# 1010829PA_HVFlyback_GD_Testboard_Overvie.net
KiCad netlist of a schematic drawn in Altium Designer
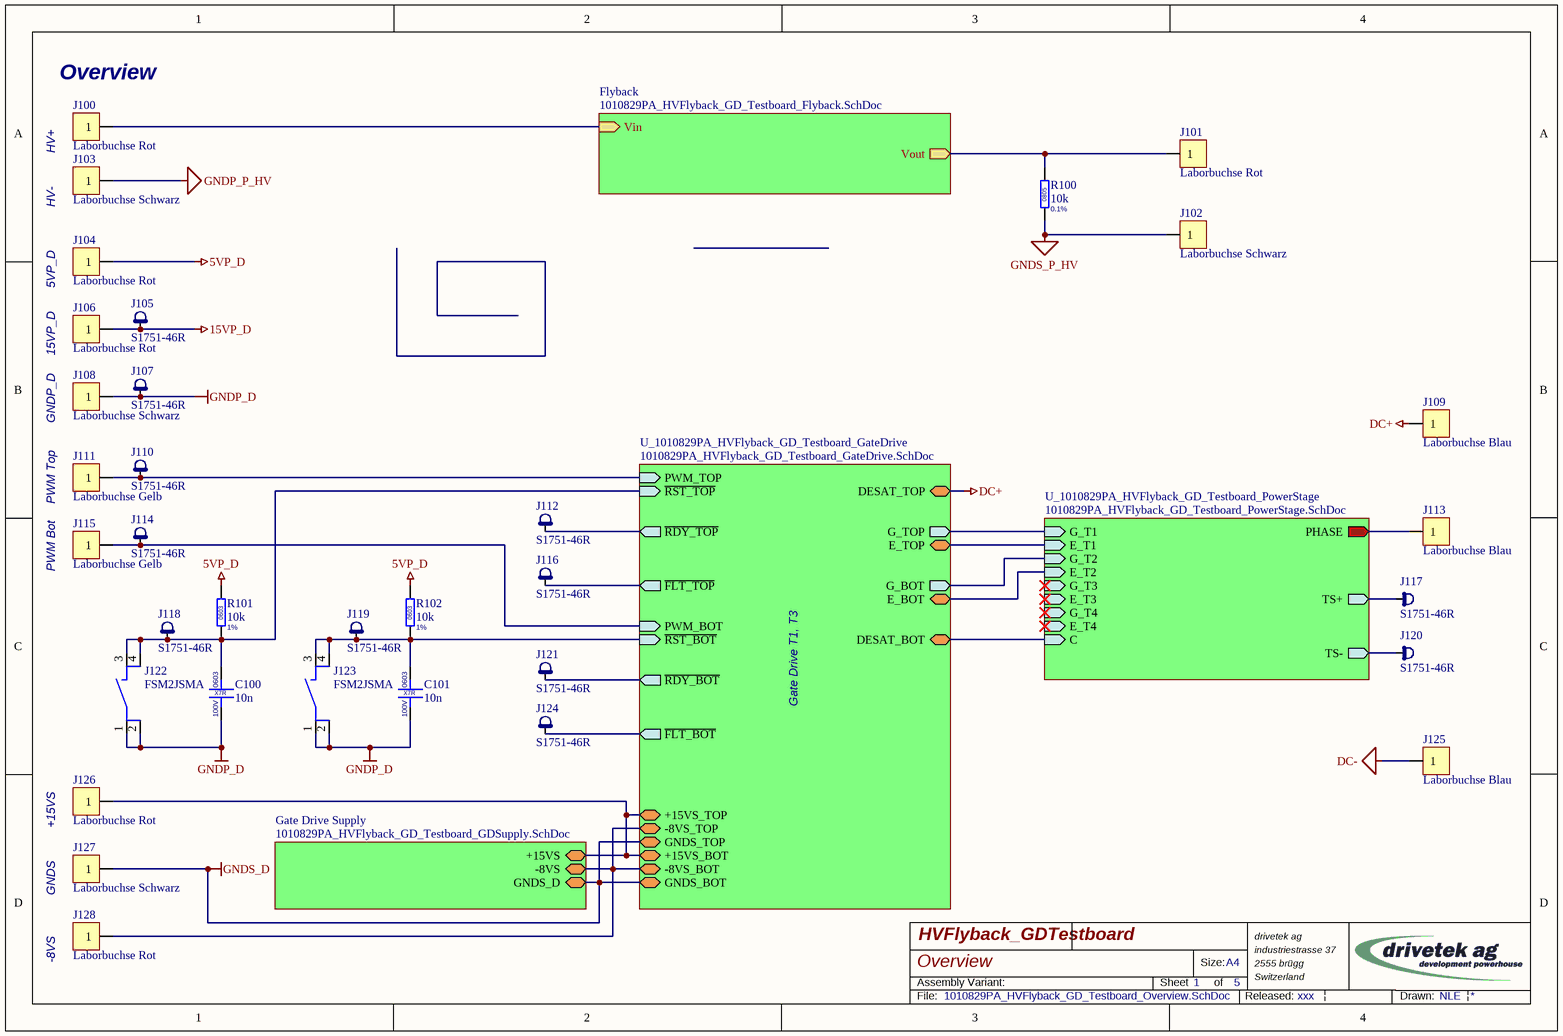
[diagram p0: 1010829PA_HVFlyback_GD_Testboard_Overview.SchDoc]

(export (version "E")
  (design (tool "Eeschema 10.0.6"))
  (components
    (comp (ref "C100")
      (value "10n")
      (footprint "02_0603_DRK_1-7x1-0x0-9")
      (fields
        (field (name "CASENAME") "0603")
        (field (name "TYPE3") "X7R")
        (field (name "VOLTAGE") "100V")
        (field (name "PART NUMBER") "02-0313")
        (field (name "TOLERANCE") "10")
        (field (name "AUTHOR") "RLE")
      )
      (libsource (lib "drivetek") (part "02_CAP"))
    )
    (comp (ref "C101")
      (value "10n")
      (footprint "02_0603_DRK_1-7x1-0x0-9")
      (fields
        (field (name "CASENAME") "0603")
        (field (name "TYPE3") "X7R")
        (field (name "VOLTAGE") "100V")
        (field (name "PART NUMBER") "02-0313")
        (field (name "TOLERANCE") "10")
        (field (name "AUTHOR") "RLE")
      )
      (libsource (lib "drivetek") (part "02_CAP"))
    )
    (comp (ref "J100")
      (value "Laborbuchse Rot")
      (footprint "13_CON_DRK_DELTRON-571-0100-4mm-Buchse")
      (fields
        (field (name "PART NUMBER") "13-0252")
        (field (name "VOLTAGE") "250V")
        (field (name "AUTHOR") "MFR")
      )
      (libsource (lib "drivetek") (part "13_CON_1"))
    )
    (comp (ref "J101")
      (value "Laborbuchse Rot")
      (footprint "13_CON_DRK_DELTRON-571-0100-4mm-Buchse")
      (fields
        (field (name "PART NUMBER") "13-0252")
        (field (name "VOLTAGE") "250V")
        (field (name "AUTHOR") "MFR")
      )
      (libsource (lib "") (part "13_CON_1_1"))
    )
    (comp (ref "J102")
      (value "Laborbuchse Schwarz")
      (footprint "13_CON_DRK_DELTRON-571-0100-4mm-Buchse")
      (fields
        (field (name "PART NUMBER") "13-0253")
        (field (name "VOLTAGE") "250V")
        (field (name "AUTHOR") "MFR")
      )
      (libsource (lib "") (part "13_CON_1_1"))
    )
    (comp (ref "J103")
      (value "Laborbuchse Schwarz")
      (footprint "13_CON_DRK_DELTRON-571-0100-4mm-Buchse")
      (fields
        (field (name "PART NUMBER") "13-0253")
        (field (name "VOLTAGE") "250V")
        (field (name "AUTHOR") "MFR")
      )
      (libsource (lib "drivetek") (part "13_CON_1"))
    )
    (comp (ref "J104")
      (value "Laborbuchse Rot")
      (footprint "13_CON_DRK_DELTRON-571-0100-4mm-Buchse")
      (fields
        (field (name "PART NUMBER") "13-0252")
        (field (name "VOLTAGE") "250V")
        (field (name "AUTHOR") "MFR")
      )
      (libsource (lib "drivetek") (part "13_CON_1"))
    )
    (comp (ref "J105")
      (value "S1751-46R")
      (footprint "13_PAD_DRK_HARWIN_S1751-46")
      (description "Probe Hook")
      (fields (field (name "PART NUMBER") "13-0487") (field (name "AUTHOR") "CSI"))
      (libsource (lib "drivetek") (part "13_ProbeHook"))
    )
    (comp (ref "J106")
      (value "Laborbuchse Rot")
      (footprint "13_CON_DRK_DELTRON-571-0100-4mm-Buchse")
      (fields
        (field (name "PART NUMBER") "13-0252")
        (field (name "VOLTAGE") "250V")
        (field (name "AUTHOR") "MFR")
      )
      (libsource (lib "drivetek") (part "13_CON_1"))
    )
    (comp (ref "J107")
      (value "S1751-46R")
      (footprint "13_PAD_DRK_HARWIN_S1751-46")
      (description "Probe Hook")
      (fields (field (name "PART NUMBER") "13-0487") (field (name "AUTHOR") "CSI"))
      (libsource (lib "drivetek") (part "13_ProbeHook"))
    )
    (comp (ref "J108")
      (value "Laborbuchse Schwarz")
      (footprint "13_CON_DRK_DELTRON-571-0100-4mm-Buchse")
      (fields
        (field (name "PART NUMBER") "13-0253")
        (field (name "VOLTAGE") "250V")
        (field (name "AUTHOR") "MFR")
      )
      (libsource (lib "drivetek") (part "13_CON_1"))
    )
    (comp (ref "J109")
      (value "Laborbuchse Blau")
      (footprint "13_CON_DRK_DELTRON-571-0100-4mm-Buchse")
      (fields
        (field (name "PART NUMBER") "13-0507")
        (field (name "VOLTAGE") "250V")
        (field (name "AUTHOR") "RLE")
      )
      (libsource (lib "") (part "13_CON_1_1"))
    )
    (comp (ref "J110")
      (value "S1751-46R")
      (footprint "13_PAD_DRK_HARWIN_S1751-46")
      (description "Probe Hook")
      (fields (field (name "PART NUMBER") "13-0487") (field (name "AUTHOR") "CSI"))
      (libsource (lib "drivetek") (part "13_ProbeHook"))
    )
    (comp (ref "J111")
      (value "Laborbuchse Gelb")
      (footprint "13_CON_DRK_DELTRON-571-0100-4mm-Buchse")
      (fields
        (field (name "PART NUMBER") "13-0506")
        (field (name "VOLTAGE") "250V")
        (field (name "AUTHOR") "RLE")
      )
      (libsource (lib "drivetek") (part "13_CON_1"))
    )
    (comp (ref "J112")
      (value "S1751-46R")
      (footprint "13_PAD_DRK_HARWIN_S1751-46")
      (description "Probe Hook")
      (fields (field (name "PART NUMBER") "13-0487") (field (name "AUTHOR") "CSI"))
      (libsource (lib "drivetek") (part "13_ProbeHook"))
    )
    (comp (ref "J113")
      (value "Laborbuchse Blau")
      (footprint "13_CON_DRK_DELTRON-571-0100-4mm-Buchse")
      (fields
        (field (name "PART NUMBER") "13-0507")
        (field (name "VOLTAGE") "250V")
        (field (name "AUTHOR") "RLE")
      )
      (libsource (lib "") (part "13_CON_1_1"))
    )
    (comp (ref "J114")
      (value "S1751-46R")
      (footprint "13_PAD_DRK_HARWIN_S1751-46")
      (description "Probe Hook")
      (fields (field (name "PART NUMBER") "13-0487") (field (name "AUTHOR") "CSI"))
      (libsource (lib "drivetek") (part "13_ProbeHook"))
    )
    (comp (ref "J115")
      (value "Laborbuchse Gelb")
      (footprint "13_CON_DRK_DELTRON-571-0100-4mm-Buchse")
      (fields
        (field (name "PART NUMBER") "13-0506")
        (field (name "VOLTAGE") "250V")
        (field (name "AUTHOR") "RLE")
      )
      (libsource (lib "drivetek") (part "13_CON_1"))
    )
    (comp (ref "J116")
      (value "S1751-46R")
      (footprint "13_PAD_DRK_HARWIN_S1751-46")
      (description "Probe Hook")
      (fields (field (name "PART NUMBER") "13-0487") (field (name "AUTHOR") "CSI"))
      (libsource (lib "drivetek") (part "13_ProbeHook"))
    )
    (comp (ref "J117")
      (value "S1751-46R")
      (footprint "13_PAD_DRK_HARWIN_S1751-46")
      (description "Probe Hook")
      (fields (field (name "PART NUMBER") "13-0487") (field (name "AUTHOR") "CSI"))
      (libsource (lib "drivetek") (part "13_ProbeHook"))
    )
    (comp (ref "J118")
      (value "S1751-46R")
      (footprint "13_PAD_DRK_HARWIN_S1751-46")
      (description "Probe Hook")
      (fields (field (name "PART NUMBER") "13-0487") (field (name "AUTHOR") "CSI"))
      (libsource (lib "drivetek") (part "13_ProbeHook"))
    )
    (comp (ref "J119")
      (value "S1751-46R")
      (footprint "13_PAD_DRK_HARWIN_S1751-46")
      (description "Probe Hook")
      (fields (field (name "PART NUMBER") "13-0487") (field (name "AUTHOR") "CSI"))
      (libsource (lib "drivetek") (part "13_ProbeHook"))
    )
    (comp (ref "J120")
      (value "S1751-46R")
      (footprint "13_PAD_DRK_HARWIN_S1751-46")
      (description "Probe Hook")
      (fields (field (name "PART NUMBER") "13-0487") (field (name "AUTHOR") "CSI"))
      (libsource (lib "drivetek") (part "13_ProbeHook"))
    )
    (comp (ref "J121")
      (value "S1751-46R")
      (footprint "13_PAD_DRK_HARWIN_S1751-46")
      (description "Probe Hook")
      (fields (field (name "PART NUMBER") "13-0487") (field (name "AUTHOR") "CSI"))
      (libsource (lib "drivetek") (part "13_ProbeHook"))
    )
    (comp (ref "J122")
      (value "FSM2JSMA")
      (footprint "10_SW_DRK_TYCO-FSM2JSMA")
      (fields
        (field (name "PART NUMBER") "10-0001")
        (field (name "VOLTAGE") "24V")
        (field (name "AUTHOR") "CBA")
      )
      (libsource (lib "drivetek") (part "10_SPNO_A12-B34"))
    )
    (comp (ref "J123")
      (value "FSM2JSMA")
      (footprint "10_SW_DRK_TYCO-FSM2JSMA")
      (fields
        (field (name "PART NUMBER") "10-0001")
        (field (name "VOLTAGE") "24V")
        (field (name "AUTHOR") "CBA")
      )
      (libsource (lib "drivetek") (part "10_SPNO_A12-B34"))
    )
    (comp (ref "J124")
      (value "S1751-46R")
      (footprint "13_PAD_DRK_HARWIN_S1751-46")
      (description "Probe Hook")
      (fields (field (name "PART NUMBER") "13-0487") (field (name "AUTHOR") "CSI"))
      (libsource (lib "drivetek") (part "13_ProbeHook"))
    )
    (comp (ref "J125")
      (value "Laborbuchse Blau")
      (footprint "13_CON_DRK_DELTRON-571-0100-4mm-Buchse")
      (fields
        (field (name "PART NUMBER") "13-0507")
        (field (name "VOLTAGE") "250V")
        (field (name "AUTHOR") "RLE")
      )
      (libsource (lib "") (part "13_CON_1_1"))
    )
    (comp (ref "J126")
      (value "Laborbuchse Rot")
      (footprint "13_CON_DRK_DELTRON-571-0100-4mm-Buchse")
      (fields
        (field (name "PART NUMBER") "13-0252")
        (field (name "VOLTAGE") "250V")
        (field (name "AUTHOR") "MFR")
      )
      (libsource (lib "drivetek") (part "13_CON_1"))
    )
    (comp (ref "J127")
      (value "Laborbuchse Schwarz")
      (footprint "13_CON_DRK_DELTRON-571-0100-4mm-Buchse")
      (fields
        (field (name "PART NUMBER") "13-0253")
        (field (name "VOLTAGE") "250V")
        (field (name "AUTHOR") "MFR")
      )
      (libsource (lib "drivetek") (part "13_CON_1"))
    )
    (comp (ref "J128")
      (value "Laborbuchse Rot")
      (footprint "13_CON_DRK_DELTRON-571-0100-4mm-Buchse")
      (fields
        (field (name "PART NUMBER") "13-0252")
        (field (name "VOLTAGE") "250V")
        (field (name "AUTHOR") "MFR")
      )
      (libsource (lib "drivetek") (part "13_CON_1"))
    )
    (comp (ref "R100")
      (value "10k")
      (footprint "01_0805_DRK_2-2x1-5x0-65")
      (fields
        (field (name "TOLERANCE") "0.1%")
        (field (name "CASENAME") "0805")
        (field (name "PART NUMBER") "01-0406")
        (field (name "VOLTAGE") "100V")
        (field (name "POWER") "100m")
        (field (name "AUTHOR") "CBA")
        (field (name "CHECKED") "HHU")
      )
      (libsource (lib "drivetek") (part "01_RES"))
    )
    (comp (ref "R101")
      (value "10k")
      (footprint "01_0603_DRK_1-7x1-0x0-55")
      (fields
        (field (name "TOLERANCE") "1%")
        (field (name "CASENAME") "0603")
        (field (name "PART NUMBER") "01-0004")
        (field (name "VOLTAGE") "50V")
        (field (name "POWER") "63m")
        (field (name "AUTHOR") "CBA")
        (field (name "CHECKED") "CBA")
      )
      (libsource (lib "drivetek") (part "01_RES"))
    )
    (comp (ref "R102")
      (value "10k")
      (footprint "01_0603_DRK_1-7x1-0x0-55")
      (fields
        (field (name "TOLERANCE") "1%")
        (field (name "CASENAME") "0603")
        (field (name "PART NUMBER") "01-0004")
        (field (name "VOLTAGE") "50V")
        (field (name "POWER") "63m")
        (field (name "AUTHOR") "CBA")
        (field (name "CHECKED") "CBA")
      )
      (libsource (lib "drivetek") (part "01_RES"))
    )
  )
  (nets
    (net (code "1") (name "/+15VS") (class "Default")
      (node (ref "J126") (pin "1") (pinfunction "1_1") (pintype "passive"))
    )
    (net (code "2") (name "/-8VS") (class "Default")
      (node (ref "J128") (pin "1") (pinfunction "1_1") (pintype "passive"))
    )
    (net (code "8") (name "/FLT_BOT") (class "Default")
      (node (ref "J124") (pin "1") (pinfunction "1_1") (pintype "passive"))
    )
    (net (code "9") (name "/FLT_TOP") (class "Default")
      (node (ref "J116") (pin "1") (pinfunction "1_1") (pintype "passive"))
    )
    (net (code "14") (name "/PHASE") (class "Default")
      (node (ref "J113") (pin "1") (pinfunction "1_1") (pintype "passive"))
    )
    (net (code "15") (name "/PWM_BOT") (class "Default")
      (node (ref "J114") (pin "1") (pinfunction "1_1") (pintype "passive"))
      (node (ref "J115") (pin "1") (pinfunction "1_1") (pintype "passive"))
    )
    (net (code "16") (name "/PWM_TOP") (class "Default")
      (node (ref "J110") (pin "1") (pinfunction "1_1") (pintype "passive"))
      (node (ref "J111") (pin "1") (pinfunction "1_1") (pintype "passive"))
    )
    (net (code "17") (name "/RDY_BOT") (class "Default")
      (node (ref "J121") (pin "1") (pinfunction "1_1") (pintype "passive"))
    )
    (net (code "18") (name "/RDY_TOP") (class "Default")
      (node (ref "J112") (pin "1") (pinfunction "1_1") (pintype "passive"))
    )
    (net (code "19") (name "/RST_BOT") (class "Default")
      (node (ref "C101") (pin "1") (pintype "passive"))
      (node (ref "J119") (pin "1") (pinfunction "1_1") (pintype "passive"))
      (node (ref "J123") (pin "3") (pinfunction "3_3") (pintype "passive"))
      (node (ref "J123") (pin "4") (pinfunction "4_4") (pintype "passive"))
      (node (ref "R102") (pin "1") (pintype "passive"))
    )
    (net (code "20") (name "/RST_TOP") (class "Default")
      (node (ref "C100") (pin "1") (pintype "passive"))
      (node (ref "J118") (pin "1") (pinfunction "1_1") (pintype "passive"))
      (node (ref "J122") (pin "3") (pinfunction "3_3") (pintype "passive"))
      (node (ref "J122") (pin "4") (pinfunction "4_4") (pintype "passive"))
      (node (ref "R101") (pin "1") (pintype "passive"))
    )
    (net (code "21") (name "/TS+") (class "Default")
      (node (ref "J117") (pin "1") (pinfunction "1_1") (pintype "passive"))
    )
    (net (code "22") (name "/TS-") (class "Default")
      (node (ref "J120") (pin "1") (pinfunction "1_1") (pintype "passive"))
    )
    (net (code "23") (name "/Vin") (class "Default")
      (node (ref "J100") (pin "1") (pinfunction "1_1") (pintype "passive"))
    )
    (net (code "24") (name "/Vout") (class "Default")
      (node (ref "J101") (pin "1") (pinfunction "1_1") (pintype "passive"))
      (node (ref "R100") (pin "2") (pintype "passive"))
    )
    (net (code "25") (name "5VP_D") (class "Default")
      (node (ref "J104") (pin "1") (pinfunction "1_1") (pintype "passive"))
      (node (ref "R101") (pin "2") (pintype "passive"))
      (node (ref "R102") (pin "2") (pintype "passive"))
    )
    (net (code "26") (name "15VP_D") (class "Default")
      (node (ref "J105") (pin "1") (pinfunction "1_1") (pintype "passive"))
      (node (ref "J106") (pin "1") (pinfunction "1_1") (pintype "passive"))
    )
    (net (code "27") (name "DC+") (class "Default")
      (node (ref "J109") (pin "1") (pinfunction "1_1") (pintype "passive"))
    )
    (net (code "28") (name "DC-") (class "Default")
      (node (ref "J125") (pin "1") (pinfunction "1_1") (pintype "passive"))
    )
    (net (code "29") (name "GNDP_D") (class "Default")
      (node (ref "C100") (pin "2") (pintype "passive"))
      (node (ref "C101") (pin "2") (pintype "passive"))
      (node (ref "J107") (pin "1") (pinfunction "1_1") (pintype "passive"))
      (node (ref "J108") (pin "1") (pinfunction "1_1") (pintype "passive"))
      (node (ref "J122") (pin "1") (pinfunction "1_1") (pintype "passive"))
      (node (ref "J122") (pin "2") (pinfunction "2_2") (pintype "passive"))
      (node (ref "J123") (pin "1") (pinfunction "1_1") (pintype "passive"))
      (node (ref "J123") (pin "2") (pinfunction "2_2") (pintype "passive"))
    )
    (net (code "30") (name "GNDP_P_HV") (class "Default")
      (node (ref "J103") (pin "1") (pinfunction "1_1") (pintype "passive"))
    )
    (net (code "31") (name "GNDS_D") (class "Default")
      (node (ref "J127") (pin "1") (pinfunction "1_1") (pintype "passive"))
    )
    (net (code "32") (name "GNDS_P_HV") (class "Default")
      (node (ref "J102") (pin "1") (pinfunction "1_1") (pintype "passive"))
      (node (ref "R100") (pin "1") (pintype "passive"))
    )
  )
)
